# pentabug_ir.net
KiCad netlist of a schematic drawn in EAGLE
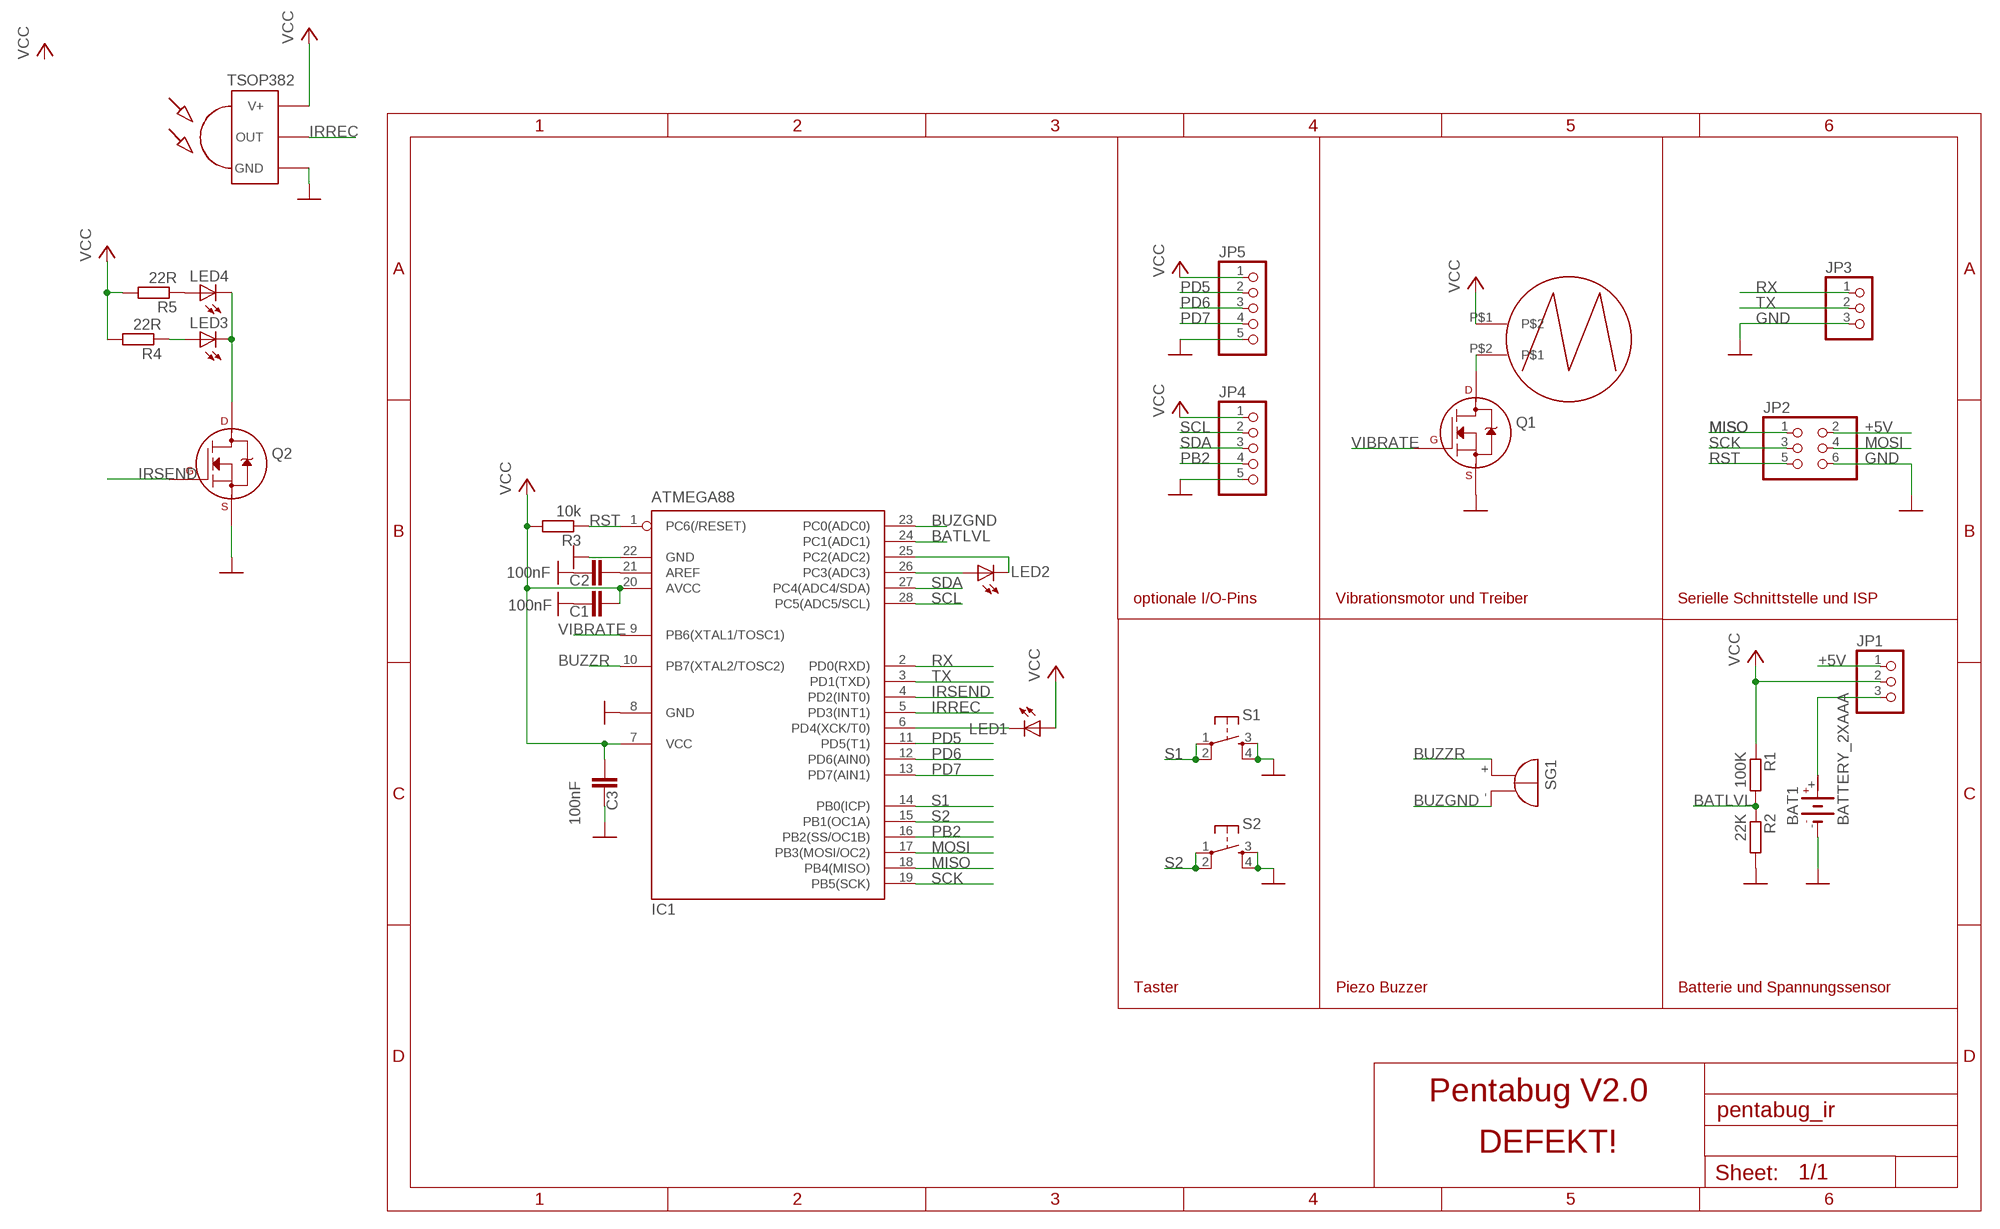
[diagram p0: schematic, sheet 1]

(export (version "E")
  (design (tool "Eeschema 10.0.6"))
  (components
    (comp (ref "BAT1")
      (value "BATTERY_2XAAA")
      (footprint "eagle-import:BATTERY_2XAAA_SMALLPINS")
      (libsource (lib "eagle-import") (part "BATTERY_2XAAA"))
    )
    (comp (ref "C1")
      (value "100nF")
      (footprint "eagle-import:C025-024X044")
      (libsource (lib "eagle-import") (part "C-EU025-024X044"))
    )
    (comp (ref "C2")
      (value "100nF")
      (footprint "eagle-import:C025-024X044")
      (libsource (lib "eagle-import") (part "C-EU025-024X044"))
    )
    (comp (ref "C3")
      (value "100nF")
      (footprint "eagle-import:C025-024X044")
      (libsource (lib "eagle-import") (part "C-EU025-024X044"))
    )
    (comp (ref "IC1")
      (value "ATMEGA88")
      (footprint "eagle-import:DIL28-3")
      (libsource (lib "eagle-import") (part "MEGA8-P"))
    )
    (comp (ref "IR")
      (value "TSOP382")
      (footprint "eagle-import:TSOP382")
      (libsource (lib "eagle-import") (part "TSOP382"))
    )
    (comp (ref "JP1")
      (value "PINHD-1X3")
      (footprint "eagle-import:1X03")
      (libsource (lib "eagle-import") (part "PINHD-1X3"))
    )
    (comp (ref "JP2")
      (value "PINHD-2X3")
      (footprint "eagle-import:2X03")
      (libsource (lib "eagle-import") (part "PINHD-2X3"))
    )
    (comp (ref "JP3")
      (value "PINHD-1X3")
      (footprint "eagle-import:1X03")
      (libsource (lib "eagle-import") (part "PINHD-1X3"))
    )
    (comp (ref "JP4")
      (value "PINHD-1X5")
      (footprint "eagle-import:1X05")
      (libsource (lib "eagle-import") (part "PINHD-1X5"))
    )
    (comp (ref "JP5")
      (value "PINHD-1X5")
      (footprint "eagle-import:1X05")
      (libsource (lib "eagle-import") (part "PINHD-1X5"))
    )
    (comp (ref "LED1")
      (value "LED5MM")
      (footprint "eagle-import:LED5MM")
      (libsource (lib "eagle-import") (part "LED5MM"))
    )
    (comp (ref "LED2")
      (value "LED5MM")
      (footprint "eagle-import:LED5MM")
      (libsource (lib "eagle-import") (part "LED5MM"))
    )
    (comp (ref "LED3")
      (value "LED3MM")
      (footprint "eagle-import:LED3MM")
      (libsource (lib "eagle-import") (part "LED3MM"))
    )
    (comp (ref "LED4")
      (value "LED3MM")
      (footprint "eagle-import:LED3MM")
      (libsource (lib "eagle-import") (part "LED3MM"))
    )
    (comp (ref "Q1")
      (value "2N7000_TO92")
      (footprint "eagle-import:TO-92")
      (libsource (lib "eagle-import") (part "2N700_TO920"))
    )
    (comp (ref "Q2")
      (value "2N7000_TO92")
      (footprint "eagle-import:TO-92")
      (libsource (lib "eagle-import") (part "2N700_TO920"))
    )
    (comp (ref "R1")
      (value "100K")
      (footprint "eagle-import:0207_10")
      (libsource (lib "eagle-import") (part "R-EU_0207/10"))
    )
    (comp (ref "R2")
      (value "22K")
      (footprint "eagle-import:0207_10")
      (libsource (lib "eagle-import") (part "R-EU_0207/10"))
    )
    (comp (ref "R3")
      (value "10k")
      (footprint "eagle-import:0207_10")
      (libsource (lib "eagle-import") (part "R-EU_0207/10"))
    )
    (comp (ref "R4")
      (value "22R")
      (footprint "eagle-import:0207_10")
      (libsource (lib "eagle-import") (part "R-EU_0207/10"))
    )
    (comp (ref "R5")
      (value "22R")
      (footprint "eagle-import:0207_10")
      (libsource (lib "eagle-import") (part "R-EU_0207/10"))
    )
    (comp (ref "S1")
      (value "TAC_SWITCHPTH")
      (footprint "eagle-import:TACTILE-PTH")
      (libsource (lib "eagle-import") (part "TAC_SWITCHPTH"))
    )
    (comp (ref "S2")
      (value "TAC_SWITCHPTH")
      (footprint "eagle-import:TACTILE-PTH")
      (libsource (lib "eagle-import") (part "TAC_SWITCHPTH"))
    )
    (comp (ref "SG1")
      (value "MULTIBUZZRTDKBUZZR")
      (footprint "eagle-import:BUZZRTDK")
      (libsource (lib "eagle-import") (part "MULTIBUZZRTDKBUZZR"))
    )
    (comp (ref "U$1")
      (value "VIBRAMOTOR")
      (footprint "eagle-import:LA4-432")
      (libsource (lib "eagle-import") (part "VIBRAMOTOR"))
    )
  )
  (nets
    (net (code "1") (name "/+5V") (class "Default")
      (node (ref "JP1") (pin "1") (pinfunction "1_1") (pintype "passive"))
      (node (ref "JP2") (pin "2") (pinfunction "2_2") (pintype "passive"))
    )
    (net (code "2") (name "/BATLVL") (class "Default")
      (node (ref "IC1") (pin "24") (pinfunction "PC1(ADC1)_24") (pintype "bidirectional"))
      (node (ref "R1") (pin "2") (pinfunction "2_2") (pintype "passive"))
      (node (ref "R2") (pin "1") (pinfunction "1_1") (pintype "passive"))
    )
    (net (code "3") (name "/BUZGND") (class "Default")
      (node (ref "IC1") (pin "23") (pinfunction "PC0(ADC0)_23") (pintype "bidirectional"))
      (node (ref "SG1") (pin "-") (pinfunction "-_-") (pintype "passive"))
    )
    (net (code "4") (name "/BUZZR") (class "Default")
      (node (ref "IC1") (pin "10") (pinfunction "PB7(XTAL2/TOSC2)_10") (pintype "bidirectional"))
      (node (ref "SG1") (pin "+") (pinfunction "+_+") (pintype "passive"))
    )
    (net (code "5") (name "/IRREC") (class "Default")
      (node (ref "IC1") (pin "5") (pinfunction "PD3(INT1)_5") (pintype "bidirectional"))
      (node (ref "IR") (pin "OUT") (pinfunction "OUT_OUT") (pintype "bidirectional"))
    )
    (net (code "6") (name "/IRSEND") (class "Default")
      (node (ref "IC1") (pin "4") (pinfunction "PD2(INT0)_4") (pintype "bidirectional"))
      (node (ref "Q2") (pin "2") (pinfunction "G_2") (pintype "tri_state"))
    )
    (net (code "7") (name "/MISO") (class "Default")
      (node (ref "IC1") (pin "18") (pinfunction "PB4(MISO)_18") (pintype "bidirectional"))
      (node (ref "JP2") (pin "1") (pinfunction "1_1") (pintype "passive"))
    )
    (net (code "8") (name "/MOSI") (class "Default")
      (node (ref "IC1") (pin "17") (pinfunction "PB3(MOSI/OC2)_17") (pintype "bidirectional"))
      (node (ref "JP2") (pin "4") (pinfunction "4_4") (pintype "passive"))
    )
    (net (code "9") (name "/PB2") (class "Default")
      (node (ref "IC1") (pin "16") (pinfunction "PB2(SS/OC1B)_16") (pintype "bidirectional"))
      (node (ref "JP4") (pin "4") (pinfunction "4_4") (pintype "passive"))
    )
    (net (code "10") (name "/PD5") (class "Default")
      (node (ref "IC1") (pin "11") (pinfunction "PD5(T1)_11") (pintype "bidirectional"))
      (node (ref "JP5") (pin "2") (pinfunction "2_2") (pintype "passive"))
    )
    (net (code "11") (name "/PD6") (class "Default")
      (node (ref "IC1") (pin "12") (pinfunction "PD6(AIN0)_12") (pintype "bidirectional"))
      (node (ref "JP5") (pin "3") (pinfunction "3_3") (pintype "passive"))
    )
    (net (code "12") (name "/PD7") (class "Default")
      (node (ref "IC1") (pin "13") (pinfunction "PD7(AIN1)_13") (pintype "bidirectional"))
      (node (ref "JP5") (pin "4") (pinfunction "4_4") (pintype "passive"))
    )
    (net (code "13") (name "/RST") (class "Default")
      (node (ref "IC1") (pin "1") (pinfunction "PC6(/RESET)_1") (pintype "bidirectional"))
      (node (ref "JP2") (pin "5") (pinfunction "5_5") (pintype "passive"))
      (node (ref "R3") (pin "1") (pinfunction "1_1") (pintype "passive"))
    )
    (net (code "14") (name "/RX") (class "Default")
      (node (ref "IC1") (pin "2") (pinfunction "PD0(RXD)_2") (pintype "bidirectional"))
      (node (ref "JP3") (pin "1") (pinfunction "1_1") (pintype "passive"))
    )
    (net (code "15") (name "/S1") (class "Default")
      (node (ref "IC1") (pin "14") (pinfunction "PB0(ICP)_14") (pintype "bidirectional"))
      (node (ref "S1") (pin "1") (pinfunction "1_1") (pintype "passive"))
      (node (ref "S1") (pin "2") (pinfunction "2_2") (pintype "passive"))
    )
    (net (code "16") (name "/S2") (class "Default")
      (node (ref "IC1") (pin "15") (pinfunction "PB1(OC1A)_15") (pintype "bidirectional"))
      (node (ref "S2") (pin "1") (pinfunction "1_1") (pintype "passive"))
      (node (ref "S2") (pin "2") (pinfunction "2_2") (pintype "passive"))
    )
    (net (code "17") (name "/SCK") (class "Default")
      (node (ref "IC1") (pin "19") (pinfunction "PB5(SCK)_19") (pintype "bidirectional"))
      (node (ref "JP2") (pin "3") (pinfunction "3_3") (pintype "passive"))
    )
    (net (code "18") (name "/SCL") (class "Default")
      (node (ref "IC1") (pin "28") (pinfunction "PC5(ADC5/SCL)_28") (pintype "bidirectional"))
      (node (ref "JP4") (pin "2") (pinfunction "2_2") (pintype "passive"))
    )
    (net (code "19") (name "/SDA") (class "Default")
      (node (ref "IC1") (pin "27") (pinfunction "PC4(ADC4/SDA)_27") (pintype "bidirectional"))
      (node (ref "JP4") (pin "3") (pinfunction "3_3") (pintype "passive"))
    )
    (net (code "20") (name "/TX") (class "Default")
      (node (ref "IC1") (pin "3") (pinfunction "PD1(TXD)_3") (pintype "bidirectional"))
      (node (ref "JP3") (pin "2") (pinfunction "2_2") (pintype "passive"))
    )
    (net (code "21") (name "/VIBRATE") (class "Default")
      (node (ref "IC1") (pin "9") (pinfunction "PB6(XTAL1/TOSC1)_9") (pintype "bidirectional"))
      (node (ref "Q1") (pin "2") (pinfunction "G_2") (pintype "tri_state"))
    )
    (net (code "22") (name "GND") (class "Default")
      (node (ref "BAT1") (pin "-") (pinfunction "-_-") (pintype "passive"))
      (node (ref "C1") (pin "1") (pinfunction "1_1") (pintype "passive"))
      (node (ref "C2") (pin "1") (pinfunction "1_1") (pintype "passive"))
      (node (ref "C3") (pin "1") (pinfunction "1_1") (pintype "passive"))
      (node (ref "IC1") (pin "22") (pinfunction "GND_22") (pintype "power_in"))
      (node (ref "IC1") (pin "8") (pinfunction "GND_8") (pintype "power_in"))
      (node (ref "IR") (pin "GND") (pinfunction "GND_GND") (pintype "bidirectional"))
      (node (ref "JP2") (pin "6") (pinfunction "6_6") (pintype "passive"))
      (node (ref "JP3") (pin "3") (pinfunction "3_3") (pintype "passive"))
      (node (ref "JP4") (pin "5") (pinfunction "5_5") (pintype "passive"))
      (node (ref "JP5") (pin "5") (pinfunction "5_5") (pintype "passive"))
      (node (ref "Q1") (pin "1") (pinfunction "S_1") (pintype "bidirectional"))
      (node (ref "Q2") (pin "1") (pinfunction "S_1") (pintype "bidirectional"))
      (node (ref "R2") (pin "2") (pinfunction "2_2") (pintype "passive"))
      (node (ref "S1") (pin "3") (pinfunction "3_3") (pintype "passive"))
      (node (ref "S1") (pin "4") (pinfunction "4_4") (pintype "passive"))
      (node (ref "S2") (pin "3") (pinfunction "3_3") (pintype "passive"))
      (node (ref "S2") (pin "4") (pinfunction "4_4") (pintype "passive"))
    )
    (net (code "23") (name "Net-(BAT1-Pad+)") (class "Default")
      (node (ref "BAT1") (pin "+") (pinfunction "+_+") (pintype "passive"))
      (node (ref "JP1") (pin "3") (pinfunction "3_3") (pintype "passive"))
    )
    (net (code "24") (name "Net-(IC1-AREF)") (class "Default")
      (node (ref "C2") (pin "2") (pinfunction "2_2") (pintype "passive"))
      (node (ref "IC1") (pin "21") (pinfunction "AREF_21") (pintype "passive"))
    )
    (net (code "25") (name "Net-(IC1-PC2(ADC2))") (class "Default")
      (node (ref "IC1") (pin "25") (pinfunction "PC2(ADC2)_25") (pintype "bidirectional"))
      (node (ref "LED2") (pin "K") (pinfunction "C_K") (pintype "passive"))
    )
    (net (code "26") (name "Net-(IC1-PC3(ADC3))") (class "Default")
      (node (ref "IC1") (pin "26") (pinfunction "PC3(ADC3)_26") (pintype "bidirectional"))
      (node (ref "LED2") (pin "A") (pinfunction "A_A") (pintype "passive"))
    )
    (net (code "27") (name "Net-(IC1-PD4(XCK{slash}T0))") (class "Default")
      (node (ref "IC1") (pin "6") (pinfunction "PD4(XCK/T0)_6") (pintype "bidirectional"))
      (node (ref "LED1") (pin "K") (pinfunction "C_K") (pintype "passive"))
    )
    (net (code "28") (name "Net-(LED3-C)") (class "Default")
      (node (ref "LED3") (pin "K") (pinfunction "C_K") (pintype "passive"))
      (node (ref "LED4") (pin "K") (pinfunction "C_K") (pintype "passive"))
      (node (ref "Q2") (pin "3") (pinfunction "D_3") (pintype "bidirectional"))
    )
    (net (code "29") (name "Net-(LED3-PadA)") (class "Default")
      (node (ref "LED3") (pin "A") (pinfunction "A_A") (pintype "passive"))
      (node (ref "R4") (pin "1") (pinfunction "1_1") (pintype "passive"))
    )
    (net (code "30") (name "Net-(LED4-PadA)") (class "Default")
      (node (ref "LED4") (pin "A") (pinfunction "A_A") (pintype "passive"))
      (node (ref "R5") (pin "1") (pinfunction "1_1") (pintype "passive"))
    )
    (net (code "31") (name "Net-(Q1-D)") (class "Default")
      (node (ref "Q1") (pin "3") (pinfunction "D_3") (pintype "bidirectional"))
      (node (ref "U$1") (pin "P$2") (pinfunction "P$1_P$2") (pintype "power_in"))
    )
    (net (code "32") (name "VCC") (class "Default")
      (node (ref "C1") (pin "2") (pinfunction "2_2") (pintype "passive"))
      (node (ref "C3") (pin "2") (pinfunction "2_2") (pintype "passive"))
      (node (ref "IC1") (pin "20") (pinfunction "AVCC_20") (pintype "power_in"))
      (node (ref "IC1") (pin "7") (pinfunction "VCC_7") (pintype "power_in"))
      (node (ref "IR") (pin "VCC") (pinfunction "V+_VCC") (pintype "bidirectional"))
      (node (ref "JP1") (pin "2") (pinfunction "2_2") (pintype "passive"))
      (node (ref "JP4") (pin "1") (pinfunction "1_1") (pintype "passive"))
      (node (ref "JP5") (pin "1") (pinfunction "1_1") (pintype "passive"))
      (node (ref "LED1") (pin "A") (pinfunction "A_A") (pintype "passive"))
      (node (ref "R1") (pin "1") (pinfunction "1_1") (pintype "passive"))
      (node (ref "R3") (pin "2") (pinfunction "2_2") (pintype "passive"))
      (node (ref "R4") (pin "2") (pinfunction "2_2") (pintype "passive"))
      (node (ref "R5") (pin "2") (pinfunction "2_2") (pintype "passive"))
      (node (ref "U$1") (pin "P$1") (pinfunction "P$2_P$1") (pintype "power_in"))
    )
  )
)
